# isoUSBtoUART.net
KiCad netlist of a schematic drawn in Altium Designer
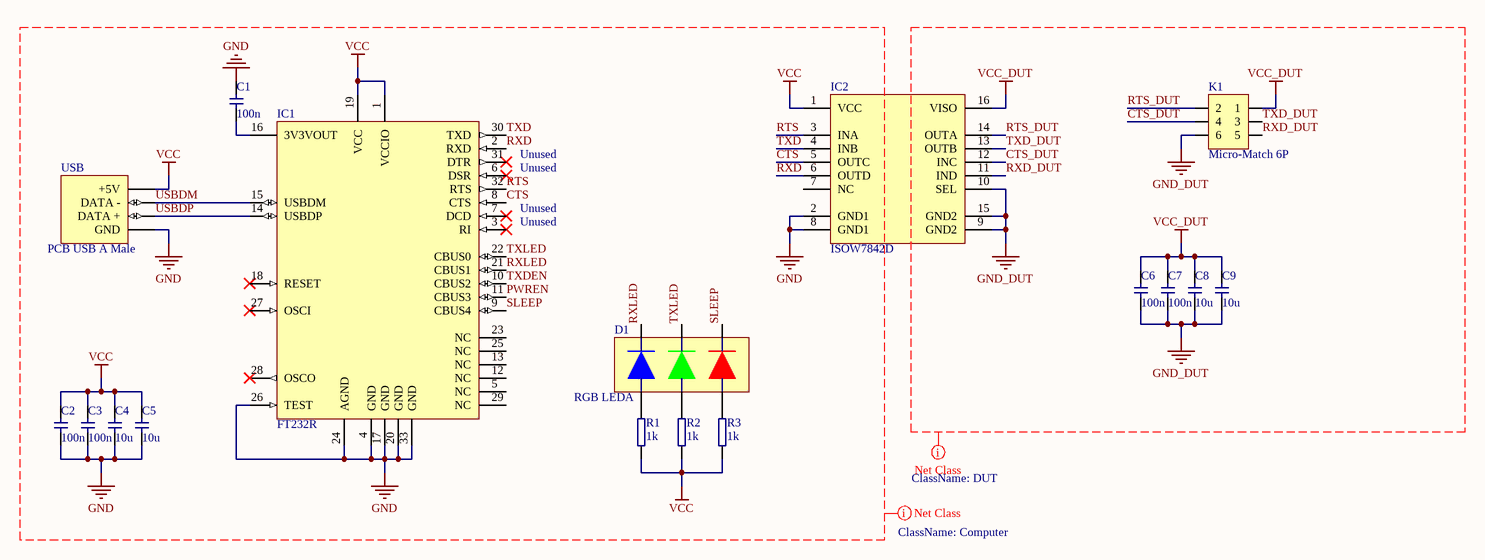
[diagram p0: isoUSBtoUART.SchDoc]

(export (version "E")
  (design (tool "Eeschema 10.0.6"))
  (components
    (comp (ref "C1")
      (value "100n")
      (footprint "CAPC0402X06N")
      (description "Capacitor")
      (libsource (lib "Schlib1") (part "Capacitor"))
    )
    (comp (ref "C2")
      (value "100n")
      (footprint "CAPC0402X06N")
      (description "Capacitor")
      (libsource (lib "Schlib1") (part "Capacitor"))
    )
    (comp (ref "C3")
      (value "100n")
      (footprint "CAPC0402X06N")
      (description "Capacitor")
      (libsource (lib "Schlib1") (part "Capacitor"))
    )
    (comp (ref "C4")
      (value "10u")
      (footprint "CAPC0402X06N")
      (description "Capacitor")
      (libsource (lib "Schlib1") (part "Capacitor"))
    )
    (comp (ref "C5")
      (value "10u")
      (footprint "CAPC0402X06N")
      (description "Capacitor")
      (libsource (lib "Schlib1") (part "Capacitor"))
    )
    (comp (ref "C6")
      (value "100n")
      (footprint "CAPC0402X06N")
      (description "Capacitor")
      (libsource (lib "Schlib1") (part "Capacitor"))
    )
    (comp (ref "C7")
      (value "100n")
      (footprint "CAPC0402X06N")
      (description "Capacitor")
      (libsource (lib "Schlib1") (part "Capacitor"))
    )
    (comp (ref "C8")
      (value "10u")
      (footprint "CAPC0402X06N")
      (description "Capacitor")
      (libsource (lib "Schlib1") (part "Capacitor"))
    )
    (comp (ref "C9")
      (value "10u")
      (footprint "CAPC0402X06N")
      (description "Capacitor")
      (libsource (lib "Schlib1") (part "Capacitor"))
    )
    (comp (ref "D1")
      (value "RGB LEDA")
      (footprint "PLCC6TRICOLLED")
      (description "RGB LED")
      (libsource (lib "Schlib1") (part "RGB LEDA"))
    )
    (comp (ref "IC1")
      (value "FT232R")
      (footprint "QFN50P500X500X100_HS-33N")
      (description "USB to USART controller")
      (libsource (lib "Schlib1") (part "FT232R"))
    )
    (comp (ref "IC2")
      (value "ISOW7842D")
      (footprint "SOIC127P1030X265-16N_ISO")
      (libsource (lib "Schlib1") (part "ISOW7842D"))
    )
    (comp (ref "K1")
      (value "Micro-Match 6P")
      (footprint "MICRO_MATCH_6P_FEMALE")
      (description "6 Pole Micro-Match connector")
      (libsource (lib "Schlib1") (part "Micro-Match 6P"))
    )
    (comp (ref "R1")
      (value "1k")
      (footprint "RESC0402X04L")
      (description "Resistor")
      (libsource (lib "Schlib1") (part "Resistor"))
    )
    (comp (ref "R2")
      (value "1k")
      (footprint "RESC0402X04L")
      (description "Resistor")
      (libsource (lib "Schlib1") (part "Resistor"))
    )
    (comp (ref "R3")
      (value "1k")
      (footprint "RESC0402X04L")
      (description "Resistor")
      (libsource (lib "Schlib1") (part "Resistor"))
    )
    (comp (ref "USB")
      (value "PCB USB A Male")
      (footprint "USB ON PCB")
      (description "On PCB USB A male connector")
      (libsource (lib "Schlib1") (part "PCB USB A Male"))
    )
  )
  (nets
    (net (code "1") (name "/CTS") (class "Default")
      (node (ref "IC1") (pin "8") (pinfunction "CTS_8") (pintype "input"))
      (node (ref "IC2") (pin "5") (pinfunction "OUTC_5") (pintype "passive"))
    )
    (net (code "2") (name "/CTS_DUT") (class "Default")
      (node (ref "IC2") (pin "12") (pinfunction "INC_12") (pintype "passive"))
      (node (ref "K1") (pin "4") (pinfunction "4_4") (pintype "passive"))
    )
    (net (code "3") (name "/PWREN") (class "Default")
      (node (ref "IC1") (pin "11") (pinfunction "CBUS3_11") (pintype "bidirectional"))
    )
    (net (code "4") (name "/RTS") (class "Default")
      (node (ref "IC1") (pin "32") (pinfunction "RTS_32") (pintype "output"))
      (node (ref "IC2") (pin "3") (pinfunction "INA_3") (pintype "passive"))
    )
    (net (code "5") (name "/RTS_DUT") (class "Default")
      (node (ref "IC2") (pin "14") (pinfunction "OUTA_14") (pintype "passive"))
      (node (ref "K1") (pin "2") (pinfunction "2_2") (pintype "passive"))
    )
    (net (code "6") (name "/RXD") (class "Default")
      (node (ref "IC1") (pin "2") (pinfunction "RXD_2") (pintype "input"))
      (node (ref "IC2") (pin "6") (pinfunction "OUTD_6") (pintype "passive"))
    )
    (net (code "7") (name "/RXD_DUT") (class "Default")
      (node (ref "IC2") (pin "11") (pinfunction "IND_11") (pintype "passive"))
      (node (ref "K1") (pin "5") (pinfunction "5_5") (pintype "passive"))
    )
    (net (code "8") (name "/RXLED") (class "Default")
      (node (ref "D1") (pin "1") (pinfunction "1_1") (pintype "passive"))
      (node (ref "IC1") (pin "21") (pinfunction "CBUS1_21") (pintype "bidirectional"))
    )
    (net (code "9") (name "/SLEEP") (class "Default")
      (node (ref "D1") (pin "3") (pinfunction "3_3") (pintype "passive"))
      (node (ref "IC1") (pin "9") (pinfunction "CBUS4_9") (pintype "bidirectional"))
    )
    (net (code "10") (name "/TXD") (class "Default")
      (node (ref "IC1") (pin "30") (pinfunction "TXD_30") (pintype "output"))
      (node (ref "IC2") (pin "4") (pinfunction "INB_4") (pintype "passive"))
    )
    (net (code "11") (name "/TXDEN") (class "Default")
      (node (ref "IC1") (pin "10") (pinfunction "CBUS2_10") (pintype "bidirectional"))
    )
    (net (code "12") (name "/TXD_DUT") (class "Default")
      (node (ref "IC2") (pin "13") (pinfunction "OUTB_13") (pintype "passive"))
      (node (ref "K1") (pin "3") (pinfunction "3_3") (pintype "passive"))
    )
    (net (code "13") (name "/TXLED") (class "Default")
      (node (ref "D1") (pin "2") (pinfunction "2_2") (pintype "passive"))
      (node (ref "IC1") (pin "22") (pinfunction "CBUS0_22") (pintype "bidirectional"))
    )
    (net (code "14") (name "/USBDM") (class "Default")
      (node (ref "IC1") (pin "15") (pinfunction "USBDM_15") (pintype "bidirectional"))
      (node (ref "USB") (pin "2") (pinfunction "DATA_-_2") (pintype "bidirectional"))
    )
    (net (code "15") (name "/USBDP") (class "Default")
      (node (ref "IC1") (pin "14") (pinfunction "USBDP_14") (pintype "bidirectional"))
      (node (ref "USB") (pin "3") (pinfunction "DATA_+_3") (pintype "bidirectional"))
    )
    (net (code "16") (name "GND") (class "Default")
      (node (ref "C1") (pin "2") (pinfunction "2_2") (pintype "passive"))
      (node (ref "C2") (pin "1") (pinfunction "1_1") (pintype "passive"))
      (node (ref "C3") (pin "1") (pinfunction "1_1") (pintype "passive"))
      (node (ref "C4") (pin "1") (pinfunction "1_1") (pintype "passive"))
      (node (ref "C5") (pin "1") (pinfunction "1_1") (pintype "passive"))
      (node (ref "IC1") (pin "17") (pinfunction "GND_17") (pintype "power_in"))
      (node (ref "IC1") (pin "20") (pinfunction "GND_20") (pintype "power_in"))
      (node (ref "IC1") (pin "24") (pinfunction "AGND_24") (pintype "power_in"))
      (node (ref "IC1") (pin "26") (pinfunction "TEST_26") (pintype "input"))
      (node (ref "IC1") (pin "33") (pinfunction "GND_33") (pintype "power_in"))
      (node (ref "IC1") (pin "4") (pinfunction "GND_4") (pintype "power_in"))
      (node (ref "IC2") (pin "2") (pinfunction "GND1_2") (pintype "passive"))
      (node (ref "IC2") (pin "8") (pinfunction "GND1_8") (pintype "passive"))
      (node (ref "USB") (pin "4") (pinfunction "GND_4") (pintype "power_in"))
    )
    (net (code "17") (name "GND_DUT") (class "Default")
      (node (ref "C6") (pin "1") (pinfunction "1_1") (pintype "passive"))
      (node (ref "C7") (pin "1") (pinfunction "1_1") (pintype "passive"))
      (node (ref "C8") (pin "1") (pinfunction "1_1") (pintype "passive"))
      (node (ref "C9") (pin "1") (pinfunction "1_1") (pintype "passive"))
      (node (ref "IC2") (pin "10") (pinfunction "SEL_10") (pintype "passive"))
      (node (ref "IC2") (pin "15") (pinfunction "GND2_15") (pintype "passive"))
      (node (ref "IC2") (pin "9") (pinfunction "GND2_9") (pintype "passive"))
      (node (ref "K1") (pin "6") (pinfunction "6_6") (pintype "passive"))
    )
    (net (code "18") (name "Net-(D1-Pad4)") (class "Default")
      (node (ref "D1") (pin "4") (pinfunction "4_4") (pintype "passive"))
      (node (ref "R3") (pin "2") (pinfunction "2_2") (pintype "passive"))
    )
    (net (code "19") (name "Net-(D1-Pad5)") (class "Default")
      (node (ref "D1") (pin "5") (pinfunction "5_5") (pintype "passive"))
      (node (ref "R2") (pin "2") (pinfunction "2_2") (pintype "passive"))
    )
    (net (code "20") (name "Net-(D1-Pad6)") (class "Default")
      (node (ref "D1") (pin "6") (pinfunction "6_6") (pintype "passive"))
      (node (ref "R1") (pin "2") (pinfunction "2_2") (pintype "passive"))
    )
    (net (code "21") (name "Net-(IC1-3V3VOUT)") (class "Default")
      (node (ref "C1") (pin "1") (pinfunction "1_1") (pintype "passive"))
      (node (ref "IC1") (pin "16") (pinfunction "3V3VOUT_16") (pintype "power_in"))
    )
    (net (code "22") (name "VCC") (class "Default")
      (node (ref "C2") (pin "2") (pinfunction "2_2") (pintype "passive"))
      (node (ref "C3") (pin "2") (pinfunction "2_2") (pintype "passive"))
      (node (ref "C4") (pin "2") (pinfunction "2_2") (pintype "passive"))
      (node (ref "C5") (pin "2") (pinfunction "2_2") (pintype "passive"))
      (node (ref "IC1") (pin "1") (pinfunction "VCCIO_1") (pintype "power_in"))
      (node (ref "IC1") (pin "19") (pinfunction "VCC_19") (pintype "power_in"))
      (node (ref "IC2") (pin "1") (pinfunction "VCC_1") (pintype "passive"))
      (node (ref "R1") (pin "1") (pinfunction "1_1") (pintype "passive"))
      (node (ref "R2") (pin "1") (pinfunction "1_1") (pintype "passive"))
      (node (ref "R3") (pin "1") (pinfunction "1_1") (pintype "passive"))
      (node (ref "USB") (pin "1") (pinfunction "+5V_1") (pintype "power_in"))
    )
    (net (code "23") (name "VCC_DUT") (class "Default")
      (node (ref "C6") (pin "2") (pinfunction "2_2") (pintype "passive"))
      (node (ref "C7") (pin "2") (pinfunction "2_2") (pintype "passive"))
      (node (ref "C8") (pin "2") (pinfunction "2_2") (pintype "passive"))
      (node (ref "C9") (pin "2") (pinfunction "2_2") (pintype "passive"))
      (node (ref "IC2") (pin "16") (pinfunction "VISO_16") (pintype "passive"))
      (node (ref "K1") (pin "1") (pinfunction "1_1") (pintype "passive"))
    )
    (net (code "24") (name "unconnected-(IC1-DCD-Pad7)") (class "Default")
      (node (ref "IC1") (pin "7") (pinfunction "DCD_7") (pintype "input+no_connect"))
    )
    (net (code "25") (name "unconnected-(IC1-DSR-Pad6)") (class "Default")
      (node (ref "IC1") (pin "6") (pinfunction "DSR_6") (pintype "input+no_connect"))
    )
    (net (code "26") (name "unconnected-(IC1-DTR-Pad31)") (class "Default")
      (node (ref "IC1") (pin "31") (pinfunction "DTR_31") (pintype "output+no_connect"))
    )
    (net (code "27") (name "unconnected-(IC1-NC-Pad5)") (class "Default")
      (node (ref "IC1") (pin "5") (pinfunction "NC_5") (pintype "passive"))
    )
    (net (code "28") (name "unconnected-(IC1-NC-Pad12)") (class "Default")
      (node (ref "IC1") (pin "12") (pinfunction "NC_12") (pintype "passive"))
    )
    (net (code "29") (name "unconnected-(IC1-NC-Pad13)") (class "Default")
      (node (ref "IC1") (pin "13") (pinfunction "NC_13") (pintype "passive"))
    )
    (net (code "30") (name "unconnected-(IC1-NC-Pad23)") (class "Default")
      (node (ref "IC1") (pin "23") (pinfunction "NC_23") (pintype "passive"))
    )
    (net (code "31") (name "unconnected-(IC1-NC-Pad25)") (class "Default")
      (node (ref "IC1") (pin "25") (pinfunction "NC_25") (pintype "passive"))
    )
    (net (code "32") (name "unconnected-(IC1-NC-Pad29)") (class "Default")
      (node (ref "IC1") (pin "29") (pinfunction "NC_29") (pintype "passive"))
    )
    (net (code "33") (name "unconnected-(IC1-OSCI-Pad27)") (class "Default")
      (node (ref "IC1") (pin "27") (pinfunction "OSCI_27") (pintype "input+no_connect"))
    )
    (net (code "34") (name "unconnected-(IC1-OSCO-Pad28)") (class "Default")
      (node (ref "IC1") (pin "28") (pinfunction "OSCO_28") (pintype "output+no_connect"))
    )
    (net (code "35") (name "unconnected-(IC1-RESET-Pad18)") (class "Default")
      (node (ref "IC1") (pin "18") (pinfunction "RESET_18") (pintype "input+no_connect"))
    )
    (net (code "36") (name "unconnected-(IC1-RI-Pad3)") (class "Default")
      (node (ref "IC1") (pin "3") (pinfunction "RI_3") (pintype "input+no_connect"))
    )
    (net (code "37") (name "unconnected-(IC2-NC-Pad7)") (class "Default")
      (node (ref "IC2") (pin "7") (pinfunction "NC_7") (pintype "passive"))
    )
  )
)
